# Voltmeter.net
KiCad netlist of a schematic drawn in EAGLE
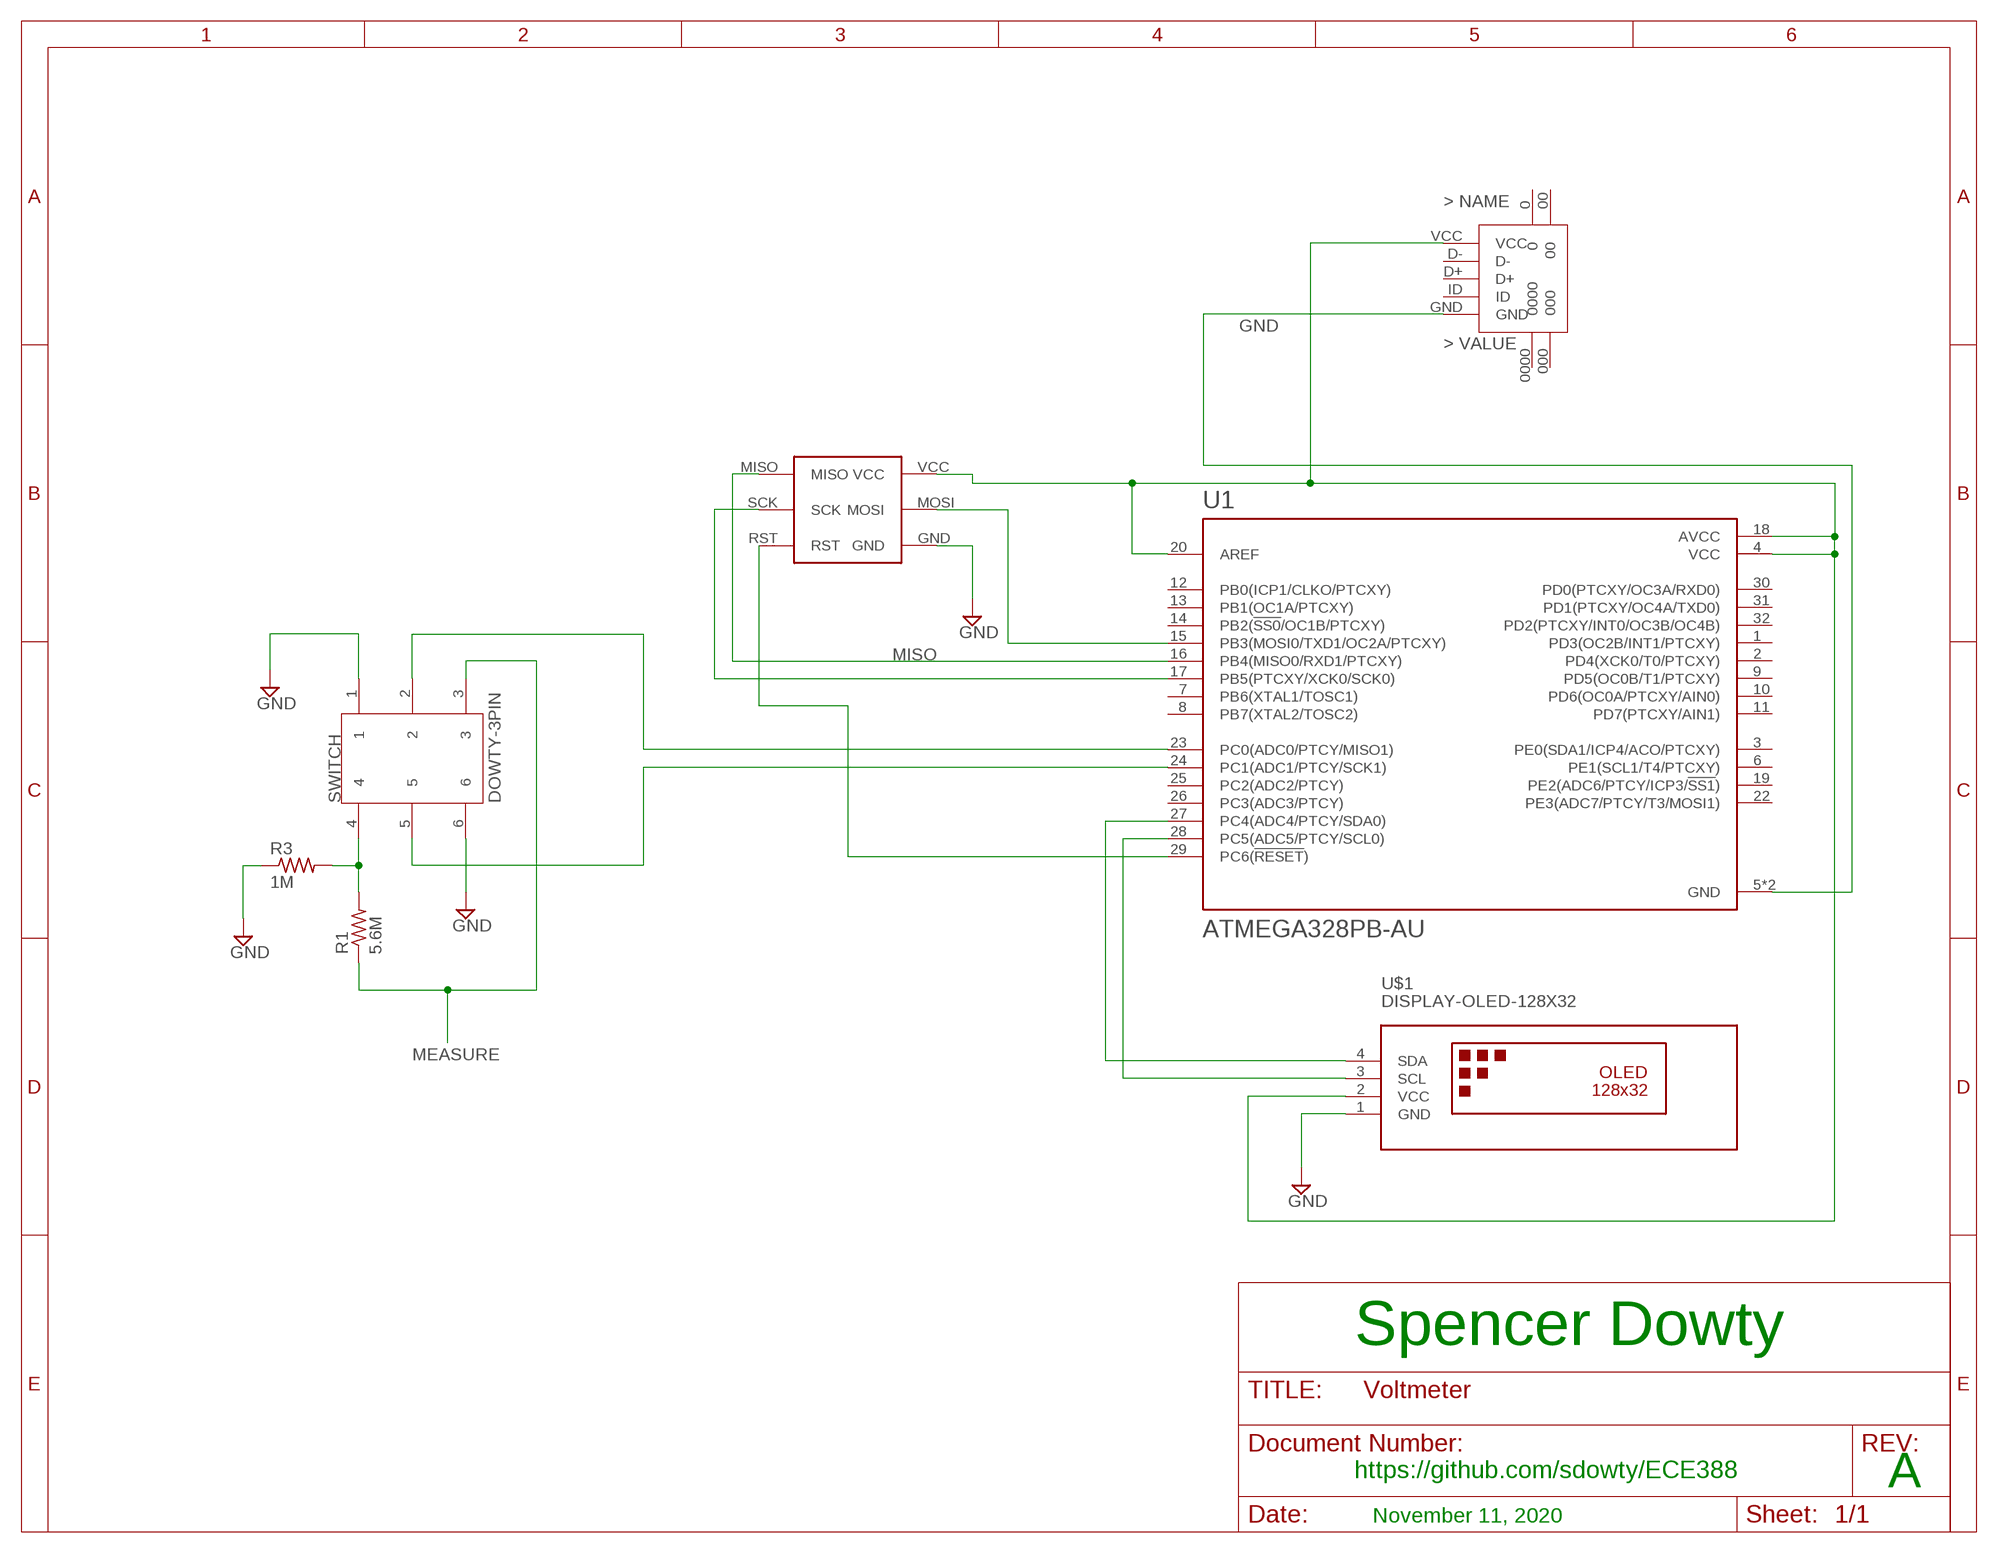
[diagram p0: schematic, sheet 1]

(export (version "E")
  (design (tool "Eeschema 10.0.6"))
  (components
    (comp (ref "6-PIN_ADAPTER")
      (value "AVR-ISP")
      (footprint "eagle-import:AVR-ISP")
      (fields (field (name "MF") "Gravitech"))
      (libsource (lib "eagle-import") (part "AVR-ISP"))
    )
    (comp (ref "MICRO-USB1")
      (value "MICRO-USB-DOWTY")
      (footprint "eagle-import:MICRO-USB-DOWTY")
      (libsource (lib "eagle-import") (part "MICRO-USB-DOWTY"))
    )
    (comp (ref "R1")
      (value "5.6M")
      (footprint "eagle-import:R0805")
      (libsource (lib "eagle-import") (part "R-US_R0805"))
    )
    (comp (ref "R3")
      (value "1M")
      (footprint "eagle-import:R0805")
      (libsource (lib "eagle-import") (part "R-US_R0805"))
    )
    (comp (ref "SWITCH")
      (value "DOWTY-3PIN")
      (footprint "eagle-import:DOWTY-3PIN")
      (libsource (lib "eagle-import") (part "DOWTY-3PIN"))
    )
    (comp (ref "U$1")
      (value "DISPLAY-OLED-128X32")
      (footprint "eagle-import:DISPLAY-OLED-128X32")
      (libsource (lib "eagle-import") (part "DISPLAY-OLED-128X32"))
    )
    (comp (ref "U1")
      (value "ATMEGA328PB-AU")
      (footprint "eagle-import:QFP80P900X900X120-32N")
      (fields (field (name "MF") "Microchip Technology / Atmel"))
      (libsource (lib "eagle-import") (part "ATMEGA328PB-AU"))
    )
  )
  (nets
    (net (code "1") (name "/MEASURE") (class "Default")
      (node (ref "R1") (pin "1") (pinfunction "1_1") (pintype "passive"))
      (node (ref "SWITCH") (pin "3") (pinfunction "3_3") (pintype "bidirectional"))
    )
    (net (code "2") (name "/MISO") (class "Default")
      (node (ref "6-PIN_ADAPTER") (pin "MISO") (pinfunction "MISO_MISO") (pintype "bidirectional"))
      (node (ref "U1") (pin "16") (pinfunction "PB4(MISO0/RXD1/PTCXY)_16") (pintype "bidirectional"))
    )
    (net (code "3") (name "GND") (class "Default")
      (node (ref "6-PIN_ADAPTER") (pin "GND") (pinfunction "GND_GND") (pintype "bidirectional"))
      (node (ref "MICRO-USB1") (pin "GND") (pinfunction "GND_GND") (pintype "bidirectional"))
      (node (ref "R3") (pin "1") (pinfunction "1_1") (pintype "passive"))
      (node (ref "SWITCH") (pin "1") (pinfunction "1_1") (pintype "bidirectional"))
      (node (ref "SWITCH") (pin "6") (pinfunction "6_6") (pintype "bidirectional"))
      (node (ref "U$1") (pin "1") (pinfunction "GND_1") (pintype "power_in"))
      (node (ref "U1") (pin "21") (pinfunction "GND_21") (pintype "power_in"))
      (node (ref "U1") (pin "5") (pinfunction "GND_5") (pintype "power_in"))
    )
    (net (code "4") (name "Net-(R1-Pad2)") (class "Default")
      (node (ref "R1") (pin "2") (pinfunction "2_2") (pintype "passive"))
      (node (ref "R3") (pin "2") (pinfunction "2_2") (pintype "passive"))
      (node (ref "SWITCH") (pin "4") (pinfunction "4_4") (pintype "bidirectional"))
    )
    (net (code "5") (name "Net-(U$1-SCL)") (class "Default")
      (node (ref "U$1") (pin "3") (pinfunction "SCL_3") (pintype "bidirectional"))
      (node (ref "U1") (pin "28") (pinfunction "PC5(ADC5/PTCY/SCL0)_28") (pintype "bidirectional"))
    )
    (net (code "6") (name "Net-(U$1-SDA)") (class "Default")
      (node (ref "U$1") (pin "4") (pinfunction "SDA_4") (pintype "bidirectional"))
      (node (ref "U1") (pin "27") (pinfunction "PC4(ADC4/PTCY/SDA0)_27") (pintype "bidirectional"))
    )
    (net (code "7") (name "Net-(U$1-VCC)") (class "Default")
      (node (ref "6-PIN_ADAPTER") (pin "VCC") (pinfunction "VCC_VCC") (pintype "bidirectional"))
      (node (ref "MICRO-USB1") (pin "VCC") (pinfunction "VCC_VCC") (pintype "bidirectional"))
      (node (ref "U$1") (pin "2") (pinfunction "VCC_2") (pintype "power_in"))
      (node (ref "U1") (pin "18") (pinfunction "AVCC_18") (pintype "power_in"))
      (node (ref "U1") (pin "20") (pinfunction "AREF_20") (pintype "input"))
      (node (ref "U1") (pin "4") (pinfunction "VCC_4") (pintype "power_in"))
    )
    (net (code "8") (name "Net-(U1-PB3(MOSI0{slash}TXD1{slash}OC2A{slash}PTCXY))") (class "Default")
      (node (ref "6-PIN_ADAPTER") (pin "MOSI") (pinfunction "MOSI_MOSI") (pintype "bidirectional"))
      (node (ref "U1") (pin "15") (pinfunction "PB3(MOSI0/TXD1/OC2A/PTCXY)_15") (pintype "bidirectional"))
    )
    (net (code "9") (name "Net-(U1-PB5(PTCXY{slash}XCK0{slash}SCK0))") (class "Default")
      (node (ref "6-PIN_ADAPTER") (pin "SCK") (pinfunction "SCK_SCK") (pintype "bidirectional"))
      (node (ref "U1") (pin "17") (pinfunction "PB5(PTCXY/XCK0/SCK0)_17") (pintype "bidirectional"))
    )
    (net (code "10") (name "Net-(U1-PC0(ADC0{slash}PTCY{slash}MISO1))") (class "Default")
      (node (ref "SWITCH") (pin "2") (pinfunction "2_2") (pintype "bidirectional"))
      (node (ref "U1") (pin "23") (pinfunction "PC0(ADC0/PTCY/MISO1)_23") (pintype "bidirectional"))
    )
    (net (code "11") (name "Net-(U1-PC1(ADC1{slash}PTCY{slash}SCK1))") (class "Default")
      (node (ref "SWITCH") (pin "5") (pinfunction "5_5") (pintype "bidirectional"))
      (node (ref "U1") (pin "24") (pinfunction "PC1(ADC1/PTCY/SCK1)_24") (pintype "bidirectional"))
    )
    (net (code "12") (name "Net-(U1-PC6(~{RESET}))") (class "Default")
      (node (ref "6-PIN_ADAPTER") (pin "RST") (pinfunction "RST_RST") (pintype "bidirectional"))
      (node (ref "U1") (pin "29") (pinfunction "PC6(~{RESET})_29") (pintype "bidirectional"))
    )
    (net (code "13") (name "unconnected-(MICRO-USB1-Pad00)") (class "Default")
      (node (ref "MICRO-USB1") (pin "00") (pinfunction "00_00") (pintype "bidirectional"))
    )
    (net (code "14") (name "unconnected-(MICRO-USB1-Pad0000)") (class "Default")
      (node (ref "MICRO-USB1") (pin "0000") (pinfunction "0000_0000") (pintype "bidirectional"))
    )
    (net (code "15") (name "unconnected-(MICRO-USB1-Pad000)") (class "Default")
      (node (ref "MICRO-USB1") (pin "000") (pinfunction "000_000") (pintype "bidirectional"))
    )
    (net (code "16") (name "unconnected-(MICRO-USB1-Pad0)") (class "Default")
      (node (ref "MICRO-USB1") (pin "0") (pinfunction "0_0") (pintype "bidirectional"))
    )
    (net (code "17") (name "unconnected-(MICRO-USB1-PadD+)") (class "Default")
      (node (ref "MICRO-USB1") (pin "D+") (pinfunction "D+_D+") (pintype "bidirectional"))
    )
    (net (code "18") (name "unconnected-(MICRO-USB1-PadD-)") (class "Default")
      (node (ref "MICRO-USB1") (pin "D-") (pinfunction "D-_D-") (pintype "bidirectional"))
    )
    (net (code "19") (name "unconnected-(MICRO-USB1-PadID)") (class "Default")
      (node (ref "MICRO-USB1") (pin "ID") (pinfunction "ID_ID") (pintype "bidirectional"))
    )
    (net (code "20") (name "unconnected-(U1-PB0(ICP1{slash}CLKO{slash}PTCXY)-Pad12)") (class "Default")
      (node (ref "U1") (pin "12") (pinfunction "PB0(ICP1/CLKO/PTCXY)_12") (pintype "bidirectional"))
    )
    (net (code "21") (name "unconnected-(U1-PB1(OC1A{slash}PTCXY)-Pad13)") (class "Default")
      (node (ref "U1") (pin "13") (pinfunction "PB1(OC1A/PTCXY)_13") (pintype "bidirectional"))
    )
    (net (code "22") (name "unconnected-(U1-PB2(~{SS0}{slash}OC1B{slash}PTCXY)-Pad14)") (class "Default")
      (node (ref "U1") (pin "14") (pinfunction "PB2(~{SS0}/OC1B/PTCXY)_14") (pintype "bidirectional"))
    )
    (net (code "23") (name "unconnected-(U1-PB6(XTAL1{slash}TOSC1)-Pad7)") (class "Default")
      (node (ref "U1") (pin "7") (pinfunction "PB6(XTAL1/TOSC1)_7") (pintype "bidirectional"))
    )
    (net (code "24") (name "unconnected-(U1-PB7(XTAL2{slash}TOSC2)-Pad8)") (class "Default")
      (node (ref "U1") (pin "8") (pinfunction "PB7(XTAL2/TOSC2)_8") (pintype "bidirectional"))
    )
    (net (code "25") (name "unconnected-(U1-PC2(ADC2{slash}PTCY)-Pad25)") (class "Default")
      (node (ref "U1") (pin "25") (pinfunction "PC2(ADC2/PTCY)_25") (pintype "bidirectional"))
    )
    (net (code "26") (name "unconnected-(U1-PC3(ADC3{slash}PTCY)-Pad26)") (class "Default")
      (node (ref "U1") (pin "26") (pinfunction "PC3(ADC3/PTCY)_26") (pintype "bidirectional"))
    )
    (net (code "27") (name "unconnected-(U1-PD0(PTCXY{slash}OC3A{slash}RXD0)-Pad30)") (class "Default")
      (node (ref "U1") (pin "30") (pinfunction "PD0(PTCXY/OC3A/RXD0)_30") (pintype "bidirectional"))
    )
    (net (code "28") (name "unconnected-(U1-PD1(PTCXY{slash}OC4A{slash}TXD0)-Pad31)") (class "Default")
      (node (ref "U1") (pin "31") (pinfunction "PD1(PTCXY/OC4A/TXD0)_31") (pintype "bidirectional"))
    )
    (net (code "29") (name "unconnected-(U1-PD2(PTCXY{slash}INT0{slash}OC3B{slash}OC4B)-Pad32)") (class "Default")
      (node (ref "U1") (pin "32") (pinfunction "PD2(PTCXY/INT0/OC3B/OC4B)_32") (pintype "bidirectional"))
    )
    (net (code "30") (name "unconnected-(U1-PD3(OC2B{slash}INT1{slash}PTCXY)-Pad1)") (class "Default")
      (node (ref "U1") (pin "1") (pinfunction "PD3(OC2B/INT1/PTCXY)_1") (pintype "bidirectional"))
    )
    (net (code "31") (name "unconnected-(U1-PD4(XCK0{slash}T0{slash}PTCXY)-Pad2)") (class "Default")
      (node (ref "U1") (pin "2") (pinfunction "PD4(XCK0/T0/PTCXY)_2") (pintype "bidirectional"))
    )
    (net (code "32") (name "unconnected-(U1-PD5(OC0B{slash}T1{slash}PTCXY)-Pad9)") (class "Default")
      (node (ref "U1") (pin "9") (pinfunction "PD5(OC0B/T1/PTCXY)_9") (pintype "bidirectional"))
    )
    (net (code "33") (name "unconnected-(U1-PD6(OC0A{slash}PTCXY{slash}AIN0)-Pad10)") (class "Default")
      (node (ref "U1") (pin "10") (pinfunction "PD6(OC0A/PTCXY/AIN0)_10") (pintype "bidirectional"))
    )
    (net (code "34") (name "unconnected-(U1-PD7(PTCXY{slash}AIN1)-Pad11)") (class "Default")
      (node (ref "U1") (pin "11") (pinfunction "PD7(PTCXY/AIN1)_11") (pintype "bidirectional"))
    )
    (net (code "35") (name "unconnected-(U1-PE0(SDA1{slash}ICP4{slash}ACO{slash}PTCXY)-Pad3)") (class "Default")
      (node (ref "U1") (pin "3") (pinfunction "PE0(SDA1/ICP4/ACO/PTCXY)_3") (pintype "bidirectional"))
    )
    (net (code "36") (name "unconnected-(U1-PE1(SCL1{slash}T4{slash}PTCXY)-Pad6)") (class "Default")
      (node (ref "U1") (pin "6") (pinfunction "PE1(SCL1/T4/PTCXY)_6") (pintype "bidirectional"))
    )
    (net (code "37") (name "unconnected-(U1-PE2(ADC6{slash}PTCY{slash}ICP3{slash}~{SS1})-Pad19)") (class "Default")
      (node (ref "U1") (pin "19") (pinfunction "PE2(ADC6/PTCY/ICP3/~{SS1})_19") (pintype "bidirectional"))
    )
    (net (code "38") (name "unconnected-(U1-PE3(ADC7{slash}PTCY{slash}T3{slash}MOSI1)-Pad22)") (class "Default")
      (node (ref "U1") (pin "22") (pinfunction "PE3(ADC7/PTCY/T3/MOSI1)_22") (pintype "bidirectional"))
    )
  )
)
